# lipo_warn.net
KiCad netlist of a schematic drawn in EAGLE
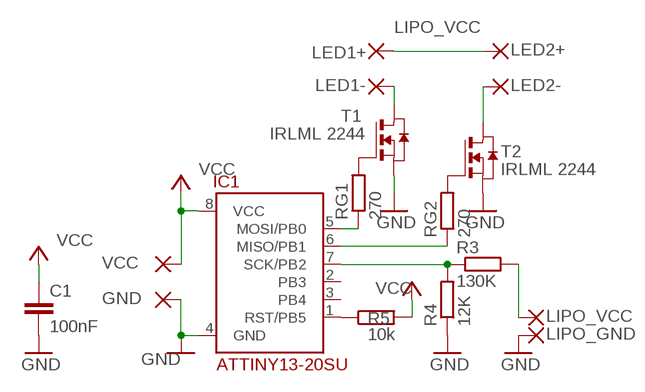
[diagram p0: schematic, sheet 1]

(export (version "E")
  (design (tool "Eeschema 10.0.6"))
  (components
    (comp (ref "C1")
      (value "100nF")
      (footprint "eagle-import:C1206")
      (libsource (lib "eagle-import") (part "C-EUC1206"))
    )
    (comp (ref "GND")
      (value "SMD2")
      (footprint "eagle-import:SMD1,27-2,54")
      (libsource (lib "eagle-import") (part "SMD2"))
    )
    (comp (ref "IC1")
      (value "ATTINY13-20SU")
      (footprint "eagle-import:SOIC8")
      (libsource (lib "eagle-import") (part "ATTINY13-20SU"))
    )
    (comp (ref "LED1+")
      (value "WIREPADSMD1,27-254")
      (footprint "eagle-import:SMD1,27-2,54")
      (libsource (lib "eagle-import") (part "WIREPADSMD1,27-254"))
    )
    (comp (ref "LED1-")
      (value "WIREPADSMD1,27-254")
      (footprint "eagle-import:SMD1,27-2,54")
      (libsource (lib "eagle-import") (part "WIREPADSMD1,27-254"))
    )
    (comp (ref "LED2+")
      (value "WIREPADSMD1,27-254")
      (footprint "eagle-import:SMD1,27-2,54")
      (libsource (lib "eagle-import") (part "WIREPADSMD1,27-254"))
    )
    (comp (ref "LED2-")
      (value "WIREPADSMD1,27-254")
      (footprint "eagle-import:SMD1,27-2,54")
      (libsource (lib "eagle-import") (part "WIREPADSMD1,27-254"))
    )
    (comp (ref "LIPO_GND")
      (value "WIREPADSMD5-2,5")
      (footprint "eagle-import:5-2,5")
      (libsource (lib "eagle-import") (part "WIREPADSMD5-2,5"))
    )
    (comp (ref "LIPO_VCC")
      (value "WIREPADSMD5-2,5")
      (footprint "eagle-import:5-2,5")
      (libsource (lib "eagle-import") (part "WIREPADSMD5-2,5"))
    )
    (comp (ref "R3")
      (value "130K")
      (footprint "eagle-import:M1206")
      (libsource (lib "eagle-import") (part "R-EU_M1206"))
    )
    (comp (ref "R4")
      (value "12K")
      (footprint "eagle-import:M1206")
      (libsource (lib "eagle-import") (part "R-EU_M1206"))
    )
    (comp (ref "R5")
      (value "10k")
      (footprint "eagle-import:M1206")
      (libsource (lib "eagle-import") (part "R-EU_M1206"))
    )
    (comp (ref "RG1")
      (value "270")
      (footprint "eagle-import:M1206")
      (libsource (lib "eagle-import") (part "R-EU_M1206"))
    )
    (comp (ref "RG2")
      (value "270")
      (footprint "eagle-import:M1206")
      (libsource (lib "eagle-import") (part "R-EU_M1206"))
    )
    (comp (ref "T1")
      (value "IRLML 2244")
      (footprint "eagle-import:SOT-23")
      (libsource (lib "eagle-import") (part "NMOSSOT23"))
    )
    (comp (ref "T2")
      (value "IRLML 2244")
      (footprint "eagle-import:SOT-23")
      (libsource (lib "eagle-import") (part "NMOSSOT23"))
    )
    (comp (ref "VCC")
      (value "SMD2")
      (footprint "eagle-import:SMD1,27-2,54")
      (libsource (lib "eagle-import") (part "SMD2"))
    )
  )
  (nets
    (net (code "1") (name "/LIPO_VCC") (class "Default")
      (node (ref "LED1+") (pin "1") (pinfunction "P_1") (pintype "passive"))
      (node (ref "LED2+") (pin "1") (pinfunction "P_1") (pintype "passive"))
    )
    (net (code "2") (name "GND") (class "Default")
      (node (ref "C1") (pin "2") (pinfunction "2_2") (pintype "passive"))
      (node (ref "GND") (pin "1") (pinfunction "P_1") (pintype "passive"))
      (node (ref "IC1") (pin "4") (pinfunction "GND_4") (pintype "power_in"))
      (node (ref "LIPO_GND") (pin "1") (pinfunction "P_1") (pintype "passive"))
      (node (ref "R4") (pin "1") (pinfunction "1_1") (pintype "passive"))
      (node (ref "T1") (pin "2") (pinfunction "S_2") (pintype "passive"))
      (node (ref "T2") (pin "2") (pinfunction "S_2") (pintype "passive"))
    )
    (net (code "3") (name "Net-(IC1-MISO{slash}PB1)") (class "Default")
      (node (ref "IC1") (pin "6") (pinfunction "MISO/PB1_6") (pintype "bidirectional"))
      (node (ref "RG2") (pin "1") (pinfunction "1_1") (pintype "passive"))
    )
    (net (code "4") (name "Net-(IC1-MOSI{slash}PB0)") (class "Default")
      (node (ref "IC1") (pin "5") (pinfunction "MOSI/PB0_5") (pintype "bidirectional"))
      (node (ref "RG1") (pin "1") (pinfunction "1_1") (pintype "passive"))
    )
    (net (code "5") (name "Net-(IC1-RST{slash}PB5)") (class "Default")
      (node (ref "IC1") (pin "1") (pinfunction "RST/PB5_1") (pintype "bidirectional"))
      (node (ref "R5") (pin "1") (pinfunction "1_1") (pintype "passive"))
    )
    (net (code "6") (name "Net-(IC1-SCK{slash}PB2)") (class "Default")
      (node (ref "IC1") (pin "7") (pinfunction "SCK/PB2_7") (pintype "bidirectional"))
      (node (ref "R3") (pin "1") (pinfunction "1_1") (pintype "passive"))
      (node (ref "R4") (pin "2") (pinfunction "2_2") (pintype "passive"))
    )
    (net (code "7") (name "Net-(LED1--P)") (class "Default")
      (node (ref "LED1-") (pin "1") (pinfunction "P_1") (pintype "passive"))
      (node (ref "T1") (pin "1") (pinfunction "D_1") (pintype "passive"))
    )
    (net (code "8") (name "Net-(LED2--P)") (class "Default")
      (node (ref "LED2-") (pin "1") (pinfunction "P_1") (pintype "passive"))
      (node (ref "T2") (pin "1") (pinfunction "D_1") (pintype "passive"))
    )
    (net (code "9") (name "Net-(LIPO_VCC-P)") (class "Default")
      (node (ref "LIPO_VCC") (pin "1") (pinfunction "P_1") (pintype "passive"))
      (node (ref "R3") (pin "2") (pinfunction "2_2") (pintype "passive"))
    )
    (net (code "10") (name "Net-(T1-G)") (class "Default")
      (node (ref "RG1") (pin "2") (pinfunction "2_2") (pintype "passive"))
      (node (ref "T1") (pin "3") (pinfunction "G_3") (pintype "passive"))
    )
    (net (code "11") (name "Net-(T2-G)") (class "Default")
      (node (ref "RG2") (pin "2") (pinfunction "2_2") (pintype "passive"))
      (node (ref "T2") (pin "3") (pinfunction "G_3") (pintype "passive"))
    )
    (net (code "12") (name "VCC") (class "Default")
      (node (ref "C1") (pin "1") (pinfunction "1_1") (pintype "passive"))
      (node (ref "IC1") (pin "8") (pinfunction "VCC_8") (pintype "power_in"))
      (node (ref "R5") (pin "2") (pinfunction "2_2") (pintype "passive"))
      (node (ref "VCC") (pin "1") (pinfunction "P_1") (pintype "passive"))
    )
    (net (code "13") (name "unconnected-(IC1-PB3-Pad2)") (class "Default")
      (node (ref "IC1") (pin "2") (pinfunction "PB3_2") (pintype "bidirectional"))
    )
    (net (code "14") (name "unconnected-(IC1-PB4-Pad3)") (class "Default")
      (node (ref "IC1") (pin "3") (pinfunction "PB4_3") (pintype "bidirectional"))
    )
  )
)
